# Rocket_Stack_Template_v1.net
KiCad netlist of a schematic drawn in Altium Designer
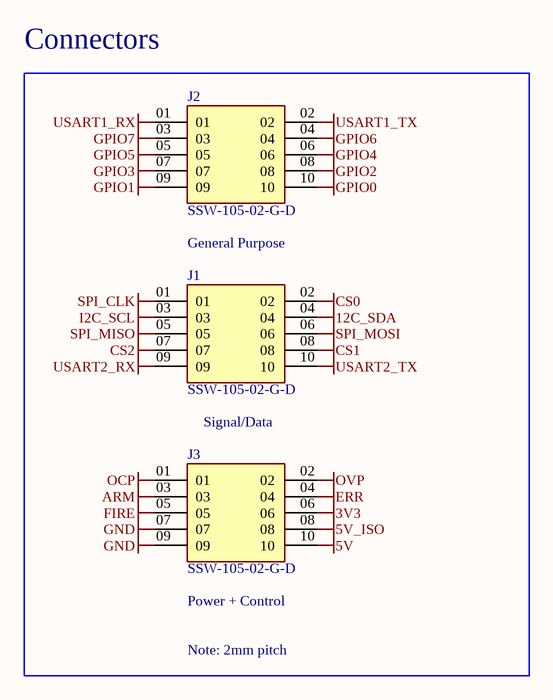
[diagram p0: Rocket_Stack_Template_v1.SchDoc]

(export (version "E")
  (design (tool "Eeschema 10.0.6"))
  (components
    (comp (ref "J1")
      (value "SSW-105-02-G-D")
      (footprint "SAMTEC_SSW-105-02-G-D")
      (fields (field (name "MF") "Samtec Inc."))
      (libsource (lib "SSW-105-02-G-D") (part "SSW-105-02-G-D"))
    )
    (comp (ref "J2")
      (value "SSW-105-02-G-D")
      (footprint "SAMTEC_SSW-105-02-G-D")
      (fields (field (name "MF") "Samtec Inc."))
      (libsource (lib "SSW-105-02-G-D") (part "SSW-105-02-G-D"))
    )
    (comp (ref "J3")
      (value "SSW-105-02-G-D")
      (footprint "SAMTEC_SSW-105-02-G-D")
      (fields (field (name "MF") "Samtec Inc."))
      (libsource (lib "SSW-105-02-G-D") (part "SSW-105-02-G-D"))
    )
  )
  (nets
    (net (code "1") (name "3V3") (class "Default")
      (node (ref "J3") (pin "06") (pinfunction "06_06") (pintype "passive"))
    )
    (net (code "2") (name "5V") (class "Default")
      (node (ref "J3") (pin "10") (pinfunction "10_10") (pintype "passive"))
    )
    (net (code "3") (name "5V_ISO") (class "Default")
      (node (ref "J3") (pin "08") (pinfunction "08_08") (pintype "passive"))
    )
    (net (code "4") (name "12C_SDA") (class "Default")
      (node (ref "J1") (pin "04") (pinfunction "04_04") (pintype "passive"))
    )
    (net (code "5") (name "ARM") (class "Default")
      (node (ref "J3") (pin "03") (pinfunction "03_03") (pintype "passive"))
    )
    (net (code "6") (name "CS0") (class "Default")
      (node (ref "J1") (pin "02") (pinfunction "02_02") (pintype "passive"))
    )
    (net (code "7") (name "CS1") (class "Default")
      (node (ref "J1") (pin "08") (pinfunction "08_08") (pintype "passive"))
    )
    (net (code "8") (name "CS2") (class "Default")
      (node (ref "J1") (pin "07") (pinfunction "07_07") (pintype "passive"))
    )
    (net (code "9") (name "ERR") (class "Default")
      (node (ref "J3") (pin "04") (pinfunction "04_04") (pintype "passive"))
    )
    (net (code "10") (name "FIRE") (class "Default")
      (node (ref "J3") (pin "05") (pinfunction "05_05") (pintype "passive"))
    )
    (net (code "11") (name "GND") (class "Default")
      (node (ref "J3") (pin "07") (pinfunction "07_07") (pintype "passive"))
      (node (ref "J3") (pin "09") (pinfunction "09_09") (pintype "passive"))
    )
    (net (code "12") (name "GPIO0") (class "Default")
      (node (ref "J2") (pin "10") (pinfunction "10_10") (pintype "passive"))
    )
    (net (code "13") (name "GPIO1") (class "Default")
      (node (ref "J2") (pin "09") (pinfunction "09_09") (pintype "passive"))
    )
    (net (code "14") (name "GPIO2") (class "Default")
      (node (ref "J2") (pin "08") (pinfunction "08_08") (pintype "passive"))
    )
    (net (code "15") (name "GPIO3") (class "Default")
      (node (ref "J2") (pin "07") (pinfunction "07_07") (pintype "passive"))
    )
    (net (code "16") (name "GPIO4") (class "Default")
      (node (ref "J2") (pin "06") (pinfunction "06_06") (pintype "passive"))
    )
    (net (code "17") (name "GPIO5") (class "Default")
      (node (ref "J2") (pin "05") (pinfunction "05_05") (pintype "passive"))
    )
    (net (code "18") (name "GPIO6") (class "Default")
      (node (ref "J2") (pin "04") (pinfunction "04_04") (pintype "passive"))
    )
    (net (code "19") (name "GPIO7") (class "Default")
      (node (ref "J2") (pin "03") (pinfunction "03_03") (pintype "passive"))
    )
    (net (code "20") (name "I2C_SCL") (class "Default")
      (node (ref "J1") (pin "03") (pinfunction "03_03") (pintype "passive"))
    )
    (net (code "21") (name "OCP") (class "Default")
      (node (ref "J3") (pin "01") (pinfunction "01_01") (pintype "passive"))
    )
    (net (code "22") (name "OVP") (class "Default")
      (node (ref "J3") (pin "02") (pinfunction "02_02") (pintype "passive"))
    )
    (net (code "23") (name "SPI_CLK") (class "Default")
      (node (ref "J1") (pin "01") (pinfunction "01_01") (pintype "passive"))
    )
    (net (code "24") (name "SPI_MISO") (class "Default")
      (node (ref "J1") (pin "05") (pinfunction "05_05") (pintype "passive"))
    )
    (net (code "25") (name "SPI_MOSI") (class "Default")
      (node (ref "J1") (pin "06") (pinfunction "06_06") (pintype "passive"))
    )
    (net (code "26") (name "USART1_RX") (class "Default")
      (node (ref "J2") (pin "01") (pinfunction "01_01") (pintype "passive"))
    )
    (net (code "27") (name "USART1_TX") (class "Default")
      (node (ref "J2") (pin "02") (pinfunction "02_02") (pintype "passive"))
    )
    (net (code "28") (name "USART2_RX") (class "Default")
      (node (ref "J1") (pin "09") (pinfunction "09_09") (pintype "passive"))
    )
    (net (code "29") (name "USART2_TX") (class "Default")
      (node (ref "J1") (pin "10") (pinfunction "10_10") (pintype "passive"))
    )
  )
)
